# BL.net
KiCad netlist of a schematic drawn in EAGLE
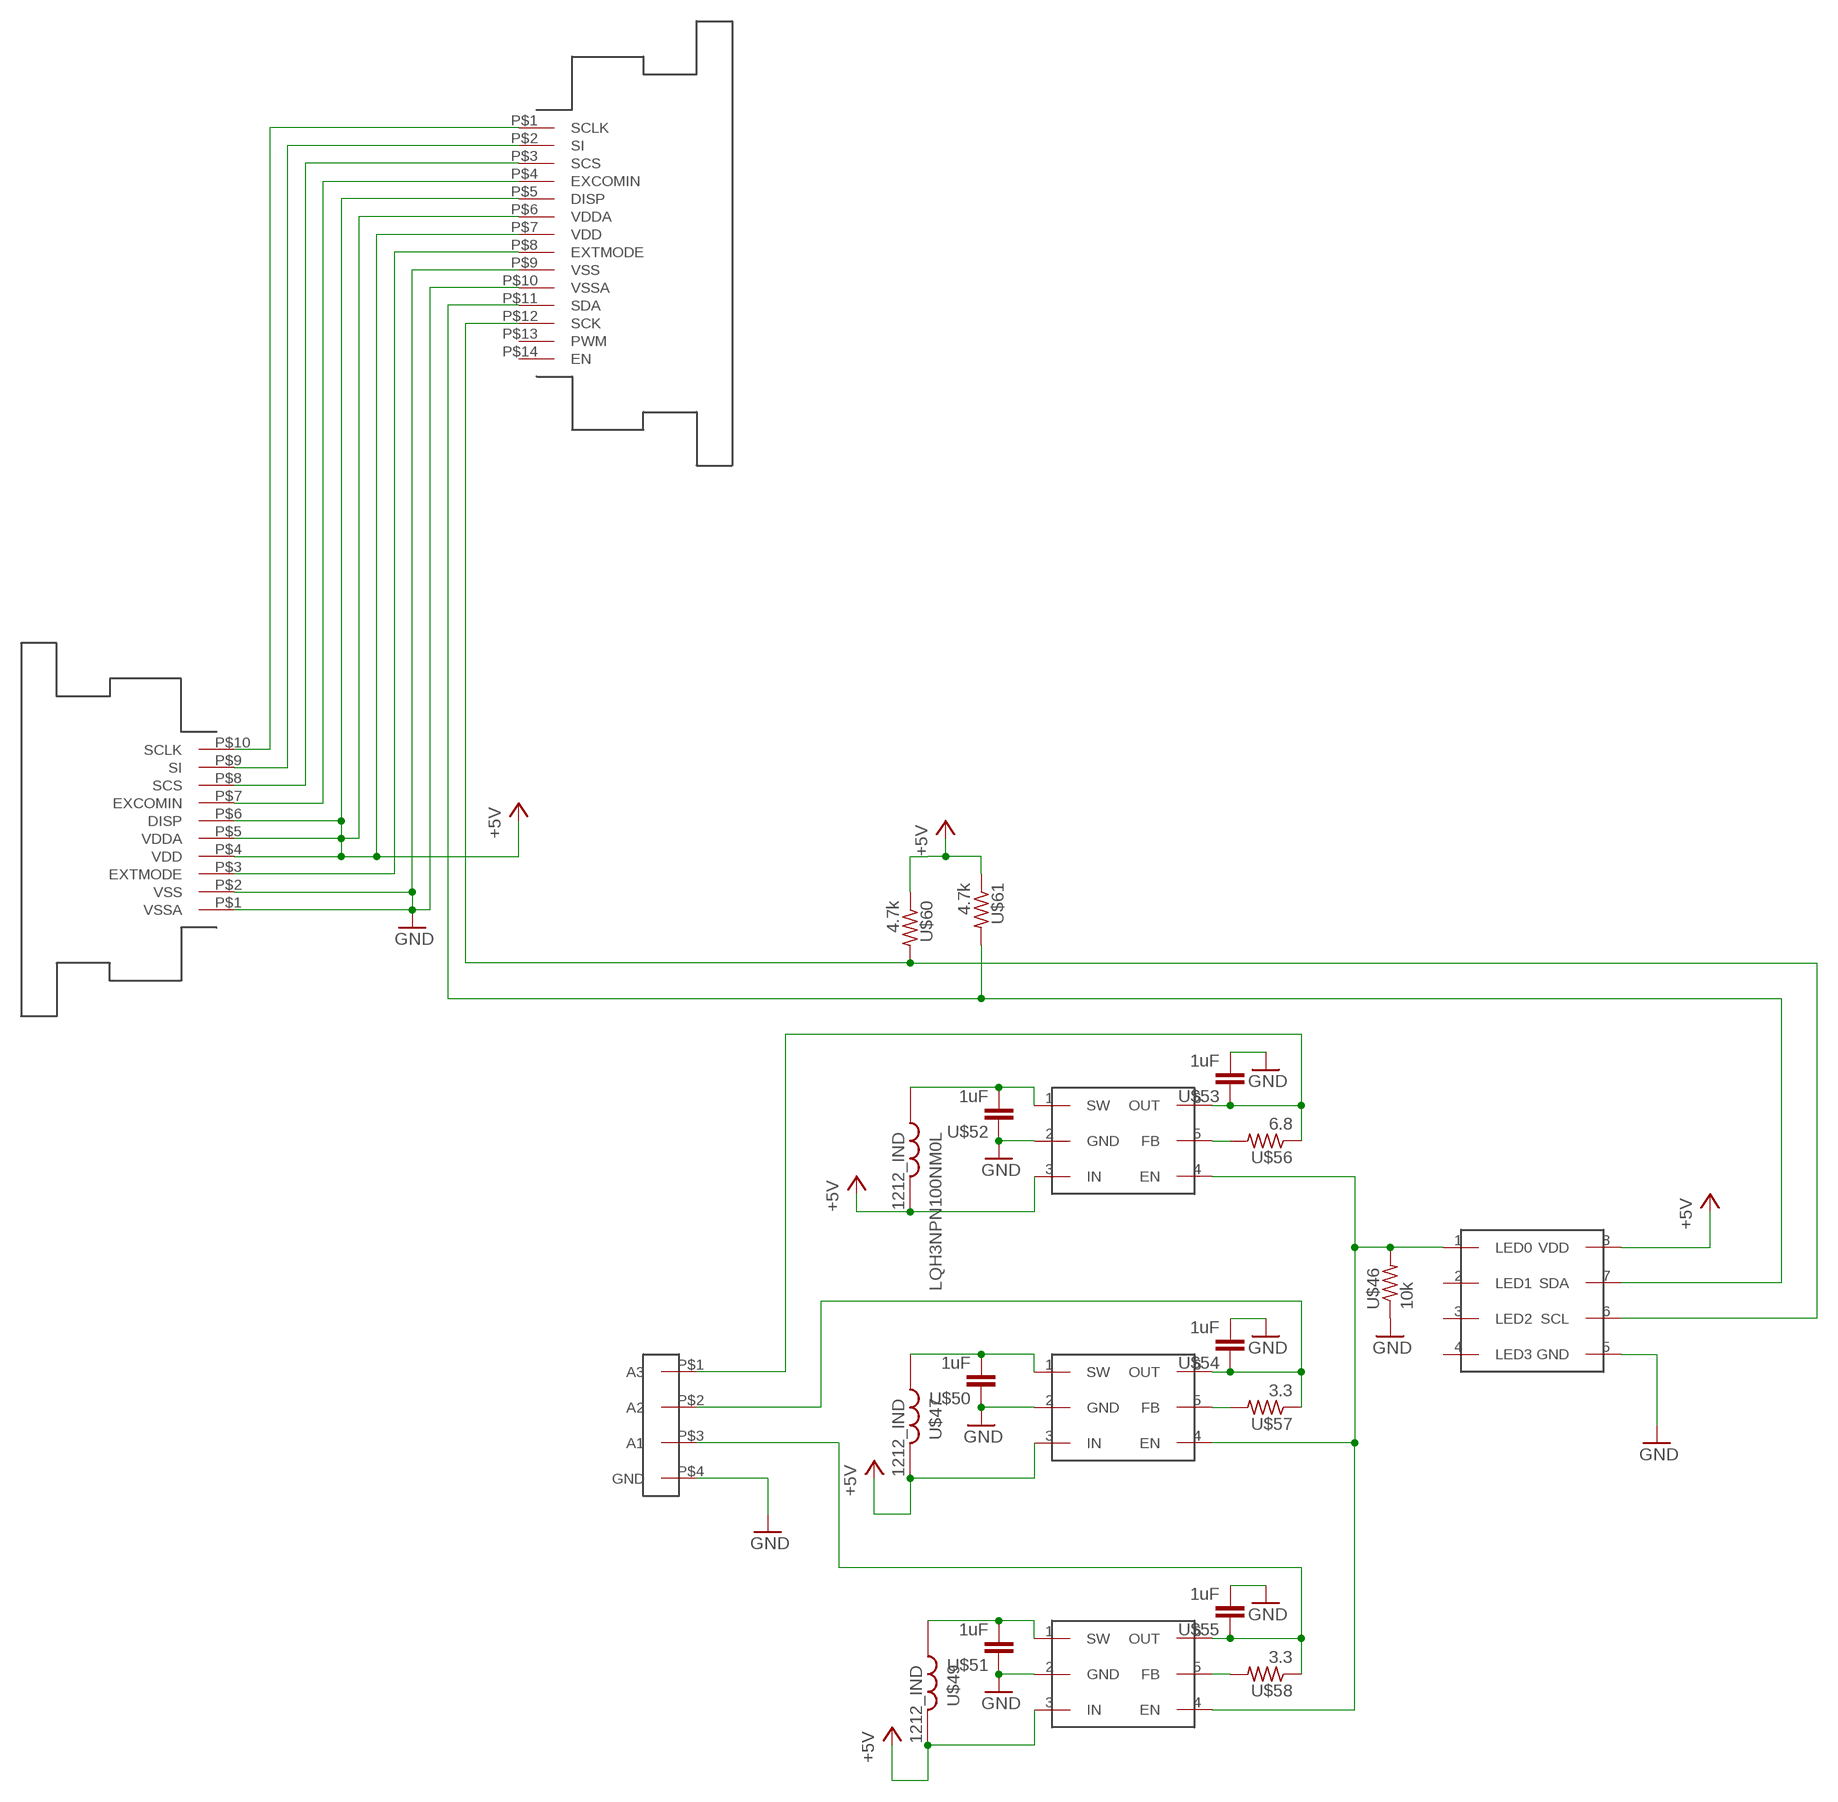
[diagram p0: schematic, sheet 1]

(export (version "E")
  (design (tool "Eeschema 10.0.6"))
  (components
    (comp (ref "LQH3NPN100NM0L")
      (value "1212_IND")
      (footprint "eagle-import:1212_IND")
      (libsource (lib "eagle-import") (part "1212_IND"))
    )
    (comp (ref "U$1")
      (value "52745-1097")
      (footprint "eagle-import:52745-1097")
      (libsource (lib "eagle-import") (part "52745-1097"))
    )
    (comp (ref "U$2")
      (value "SFV14R-2STE1HLF")
      (footprint "eagle-import:SFV14R-2STE1HLF")
      (libsource (lib "eagle-import") (part "SFV14R-2STE1HLF"))
    )
    (comp (ref "U$36")
      (value "SC4541")
      (footprint "eagle-import:SOT23-6")
      (libsource (lib "eagle-import") (part "SC4541"))
    )
    (comp (ref "U$37")
      (value "SC4541")
      (footprint "eagle-import:SOT23-6")
      (libsource (lib "eagle-import") (part "SC4541"))
    )
    (comp (ref "U$44")
      (value "SC4541")
      (footprint "eagle-import:SOT23-6")
      (libsource (lib "eagle-import") (part "SC4541"))
    )
    (comp (ref "U$45")
      (value "PCA9632DP1")
      (footprint "eagle-import:TSSOP-8")
      (libsource (lib "eagle-import") (part "PCA9632DP1"))
    )
    (comp (ref "U$46")
      (value "10k")
      (footprint "eagle-import:RF-C0805")
      (libsource (lib "eagle-import") (part "RF-R0805"))
    )
    (comp (ref "U$47")
      (value "1212_IND")
      (footprint "eagle-import:1212_IND")
      (libsource (lib "eagle-import") (part "1212_IND"))
    )
    (comp (ref "U$49")
      (value "1212_IND")
      (footprint "eagle-import:1212_IND")
      (libsource (lib "eagle-import") (part "1212_IND"))
    )
    (comp (ref "U$50")
      (value "1uF")
      (footprint "eagle-import:C0805")
      (libsource (lib "eagle-import") (part "RF-C0805"))
    )
    (comp (ref "U$51")
      (value "1uF")
      (footprint "eagle-import:C0805")
      (libsource (lib "eagle-import") (part "RF-C0805"))
    )
    (comp (ref "U$52")
      (value "1uF")
      (footprint "eagle-import:C0805")
      (libsource (lib "eagle-import") (part "RF-C0805"))
    )
    (comp (ref "U$53")
      (value "1uF")
      (footprint "eagle-import:C0805")
      (libsource (lib "eagle-import") (part "RF-C0805"))
    )
    (comp (ref "U$54")
      (value "1uF")
      (footprint "eagle-import:C0805")
      (libsource (lib "eagle-import") (part "RF-C0805"))
    )
    (comp (ref "U$55")
      (value "1uF")
      (footprint "eagle-import:C0805")
      (libsource (lib "eagle-import") (part "RF-C0805"))
    )
    (comp (ref "U$56")
      (value "6.8")
      (footprint "eagle-import:RF-C0805")
      (libsource (lib "eagle-import") (part "RF-R0805"))
    )
    (comp (ref "U$57")
      (value "3.3")
      (footprint "eagle-import:RF-C0805")
      (libsource (lib "eagle-import") (part "RF-R0805"))
    )
    (comp (ref "U$58")
      (value "3.3")
      (footprint "eagle-import:RF-C0805")
      (libsource (lib "eagle-import") (part "RF-R0805"))
    )
    (comp (ref "U$59")
      (value "BL_CONSOLDER")
      (footprint "eagle-import:S9091-46R")
      (libsource (lib "eagle-import") (part "BL_CONSOLDER"))
    )
    (comp (ref "U$60")
      (value "4.7k")
      (footprint "eagle-import:RF-C0805")
      (libsource (lib "eagle-import") (part "RF-R0805"))
    )
    (comp (ref "U$61")
      (value "4.7k")
      (footprint "eagle-import:RF-C0805")
      (libsource (lib "eagle-import") (part "RF-R0805"))
    )
  )
  (nets
    (net (code "1") (name "+5V") (class "Default")
      (node (ref "LQH3NPN100NM0L") (pin "P$1") (pinfunction "1_P$1") (pintype "bidirectional"))
      (node (ref "U$1") (pin "P$4") (pinfunction "VDD_P$4") (pintype "bidirectional"))
      (node (ref "U$1") (pin "P$5") (pinfunction "VDDA_P$5") (pintype "bidirectional"))
      (node (ref "U$1") (pin "P$6") (pinfunction "DISP_P$6") (pintype "bidirectional"))
      (node (ref "U$2") (pin "P$5") (pinfunction "DISP_P$5") (pintype "bidirectional"))
      (node (ref "U$2") (pin "P$6") (pinfunction "VDDA_P$6") (pintype "bidirectional"))
      (node (ref "U$2") (pin "P$7") (pinfunction "VDD_P$7") (pintype "bidirectional"))
      (node (ref "U$36") (pin "3") (pinfunction "IN_3") (pintype "bidirectional"))
      (node (ref "U$37") (pin "3") (pinfunction "IN_3") (pintype "bidirectional"))
      (node (ref "U$44") (pin "3") (pinfunction "IN_3") (pintype "bidirectional"))
      (node (ref "U$45") (pin "8") (pinfunction "VDD_8") (pintype "bidirectional"))
      (node (ref "U$47") (pin "P$1") (pinfunction "1_P$1") (pintype "bidirectional"))
      (node (ref "U$49") (pin "P$1") (pinfunction "1_P$1") (pintype "bidirectional"))
      (node (ref "U$60") (pin "1") (pinfunction "1_1") (pintype "passive"))
      (node (ref "U$61") (pin "1") (pinfunction "1_1") (pintype "passive"))
    )
    (net (code "2") (name "GND") (class "Default")
      (node (ref "U$1") (pin "P$1") (pinfunction "VSSA_P$1") (pintype "bidirectional"))
      (node (ref "U$1") (pin "P$2") (pinfunction "VSS_P$2") (pintype "bidirectional"))
      (node (ref "U$2") (pin "P$10") (pinfunction "VSSA_P$10") (pintype "bidirectional"))
      (node (ref "U$2") (pin "P$9") (pinfunction "VSS_P$9") (pintype "bidirectional"))
      (node (ref "U$36") (pin "2") (pinfunction "GND_2") (pintype "bidirectional"))
      (node (ref "U$37") (pin "2") (pinfunction "GND_2") (pintype "bidirectional"))
      (node (ref "U$44") (pin "2") (pinfunction "GND_2") (pintype "bidirectional"))
      (node (ref "U$45") (pin "5") (pinfunction "GND_5") (pintype "bidirectional"))
      (node (ref "U$46") (pin "1") (pinfunction "1_1") (pintype "passive"))
      (node (ref "U$50") (pin "1") (pinfunction "1_1") (pintype "passive"))
      (node (ref "U$51") (pin "1") (pinfunction "1_1") (pintype "passive"))
      (node (ref "U$52") (pin "1") (pinfunction "1_1") (pintype "passive"))
      (node (ref "U$53") (pin "2") (pinfunction "2_2") (pintype "passive"))
      (node (ref "U$54") (pin "2") (pinfunction "2_2") (pintype "passive"))
      (node (ref "U$55") (pin "2") (pinfunction "2_2") (pintype "passive"))
      (node (ref "U$59") (pin "P$4") (pinfunction "GND_P$4") (pintype "bidirectional"))
    )
    (net (code "3") (name "Net-(LQH3NPN100NM0L-2)") (class "Default")
      (node (ref "LQH3NPN100NM0L") (pin "P$2") (pinfunction "2_P$2") (pintype "bidirectional"))
      (node (ref "U$36") (pin "1") (pinfunction "SW_1") (pintype "bidirectional"))
      (node (ref "U$52") (pin "2") (pinfunction "2_2") (pintype "passive"))
    )
    (net (code "4") (name "Net-(U$1-EXCOMIN)") (class "Default")
      (node (ref "U$1") (pin "P$7") (pinfunction "EXCOMIN_P$7") (pintype "bidirectional"))
      (node (ref "U$2") (pin "P$4") (pinfunction "EXCOMIN_P$4") (pintype "bidirectional"))
    )
    (net (code "5") (name "Net-(U$1-EXTMODE)") (class "Default")
      (node (ref "U$1") (pin "P$3") (pinfunction "EXTMODE_P$3") (pintype "bidirectional"))
      (node (ref "U$2") (pin "P$8") (pinfunction "EXTMODE_P$8") (pintype "bidirectional"))
    )
    (net (code "6") (name "Net-(U$1-SCLK)") (class "Default")
      (node (ref "U$1") (pin "P$10") (pinfunction "SCLK_P$10") (pintype "bidirectional"))
      (node (ref "U$2") (pin "P$1") (pinfunction "SCLK_P$1") (pintype "bidirectional"))
    )
    (net (code "7") (name "Net-(U$1-SCS)") (class "Default")
      (node (ref "U$1") (pin "P$8") (pinfunction "SCS_P$8") (pintype "bidirectional"))
      (node (ref "U$2") (pin "P$3") (pinfunction "SCS_P$3") (pintype "bidirectional"))
    )
    (net (code "8") (name "Net-(U$1-SI)") (class "Default")
      (node (ref "U$1") (pin "P$9") (pinfunction "SI_P$9") (pintype "bidirectional"))
      (node (ref "U$2") (pin "P$2") (pinfunction "SI_P$2") (pintype "bidirectional"))
    )
    (net (code "9") (name "Net-(U$2-SCK)") (class "Default")
      (node (ref "U$2") (pin "P$12") (pinfunction "SCK_P$12") (pintype "bidirectional"))
      (node (ref "U$45") (pin "6") (pinfunction "SCL_6") (pintype "bidirectional"))
      (node (ref "U$60") (pin "2") (pinfunction "2_2") (pintype "passive"))
    )
    (net (code "10") (name "Net-(U$2-SDA)") (class "Default")
      (node (ref "U$2") (pin "P$11") (pinfunction "SDA_P$11") (pintype "bidirectional"))
      (node (ref "U$45") (pin "7") (pinfunction "SDA_7") (pintype "bidirectional"))
      (node (ref "U$61") (pin "2") (pinfunction "2_2") (pintype "passive"))
    )
    (net (code "11") (name "Net-(U$36-EN)") (class "Default")
      (node (ref "U$36") (pin "4") (pinfunction "EN_4") (pintype "bidirectional"))
      (node (ref "U$37") (pin "4") (pinfunction "EN_4") (pintype "bidirectional"))
      (node (ref "U$44") (pin "4") (pinfunction "EN_4") (pintype "bidirectional"))
      (node (ref "U$45") (pin "1") (pinfunction "LED0_1") (pintype "bidirectional"))
      (node (ref "U$46") (pin "2") (pinfunction "2_2") (pintype "passive"))
    )
    (net (code "12") (name "Net-(U$36-FB)") (class "Default")
      (node (ref "U$36") (pin "5") (pinfunction "FB_5") (pintype "bidirectional"))
      (node (ref "U$56") (pin "2") (pinfunction "2_2") (pintype "passive"))
    )
    (net (code "13") (name "Net-(U$36-OUT)") (class "Default")
      (node (ref "U$36") (pin "6") (pinfunction "OUT_6") (pintype "bidirectional"))
      (node (ref "U$53") (pin "1") (pinfunction "1_1") (pintype "passive"))
      (node (ref "U$56") (pin "1") (pinfunction "1_1") (pintype "passive"))
      (node (ref "U$59") (pin "P$1") (pinfunction "A3_P$1") (pintype "bidirectional"))
    )
    (net (code "14") (name "Net-(U$37-FB)") (class "Default")
      (node (ref "U$37") (pin "5") (pinfunction "FB_5") (pintype "bidirectional"))
      (node (ref "U$57") (pin "2") (pinfunction "2_2") (pintype "passive"))
    )
    (net (code "15") (name "Net-(U$37-OUT)") (class "Default")
      (node (ref "U$37") (pin "6") (pinfunction "OUT_6") (pintype "bidirectional"))
      (node (ref "U$54") (pin "1") (pinfunction "1_1") (pintype "passive"))
      (node (ref "U$57") (pin "1") (pinfunction "1_1") (pintype "passive"))
      (node (ref "U$59") (pin "P$2") (pinfunction "A2_P$2") (pintype "bidirectional"))
    )
    (net (code "16") (name "Net-(U$37-SW)") (class "Default")
      (node (ref "U$37") (pin "1") (pinfunction "SW_1") (pintype "bidirectional"))
      (node (ref "U$47") (pin "P$2") (pinfunction "2_P$2") (pintype "bidirectional"))
      (node (ref "U$50") (pin "2") (pinfunction "2_2") (pintype "passive"))
    )
    (net (code "17") (name "Net-(U$44-FB)") (class "Default")
      (node (ref "U$44") (pin "5") (pinfunction "FB_5") (pintype "bidirectional"))
      (node (ref "U$58") (pin "2") (pinfunction "2_2") (pintype "passive"))
    )
    (net (code "18") (name "Net-(U$44-OUT)") (class "Default")
      (node (ref "U$44") (pin "6") (pinfunction "OUT_6") (pintype "bidirectional"))
      (node (ref "U$55") (pin "1") (pinfunction "1_1") (pintype "passive"))
      (node (ref "U$58") (pin "1") (pinfunction "1_1") (pintype "passive"))
      (node (ref "U$59") (pin "P$3") (pinfunction "A1_P$3") (pintype "bidirectional"))
    )
    (net (code "19") (name "Net-(U$44-SW)") (class "Default")
      (node (ref "U$44") (pin "1") (pinfunction "SW_1") (pintype "bidirectional"))
      (node (ref "U$49") (pin "P$2") (pinfunction "2_P$2") (pintype "bidirectional"))
      (node (ref "U$51") (pin "2") (pinfunction "2_2") (pintype "passive"))
    )
    (net (code "20") (name "unconnected-(U$2-EN-PadP$14)") (class "Default")
      (node (ref "U$2") (pin "P$14") (pinfunction "EN_P$14") (pintype "bidirectional"))
    )
    (net (code "21") (name "unconnected-(U$2-PWM-PadP$13)") (class "Default")
      (node (ref "U$2") (pin "P$13") (pinfunction "PWM_P$13") (pintype "bidirectional"))
    )
    (net (code "22") (name "unconnected-(U$45-LED1-Pad2)") (class "Default")
      (node (ref "U$45") (pin "2") (pinfunction "LED1_2") (pintype "bidirectional"))
    )
    (net (code "23") (name "unconnected-(U$45-LED2-Pad3)") (class "Default")
      (node (ref "U$45") (pin "3") (pinfunction "LED2_3") (pintype "bidirectional"))
    )
    (net (code "24") (name "unconnected-(U$45-LED3-Pad4)") (class "Default")
      (node (ref "U$45") (pin "4") (pinfunction "LED3_4") (pintype "bidirectional"))
    )
  )
)
